# STM32F030C8T6.net
KiCad netlist of a schematic drawn in Altium Designer
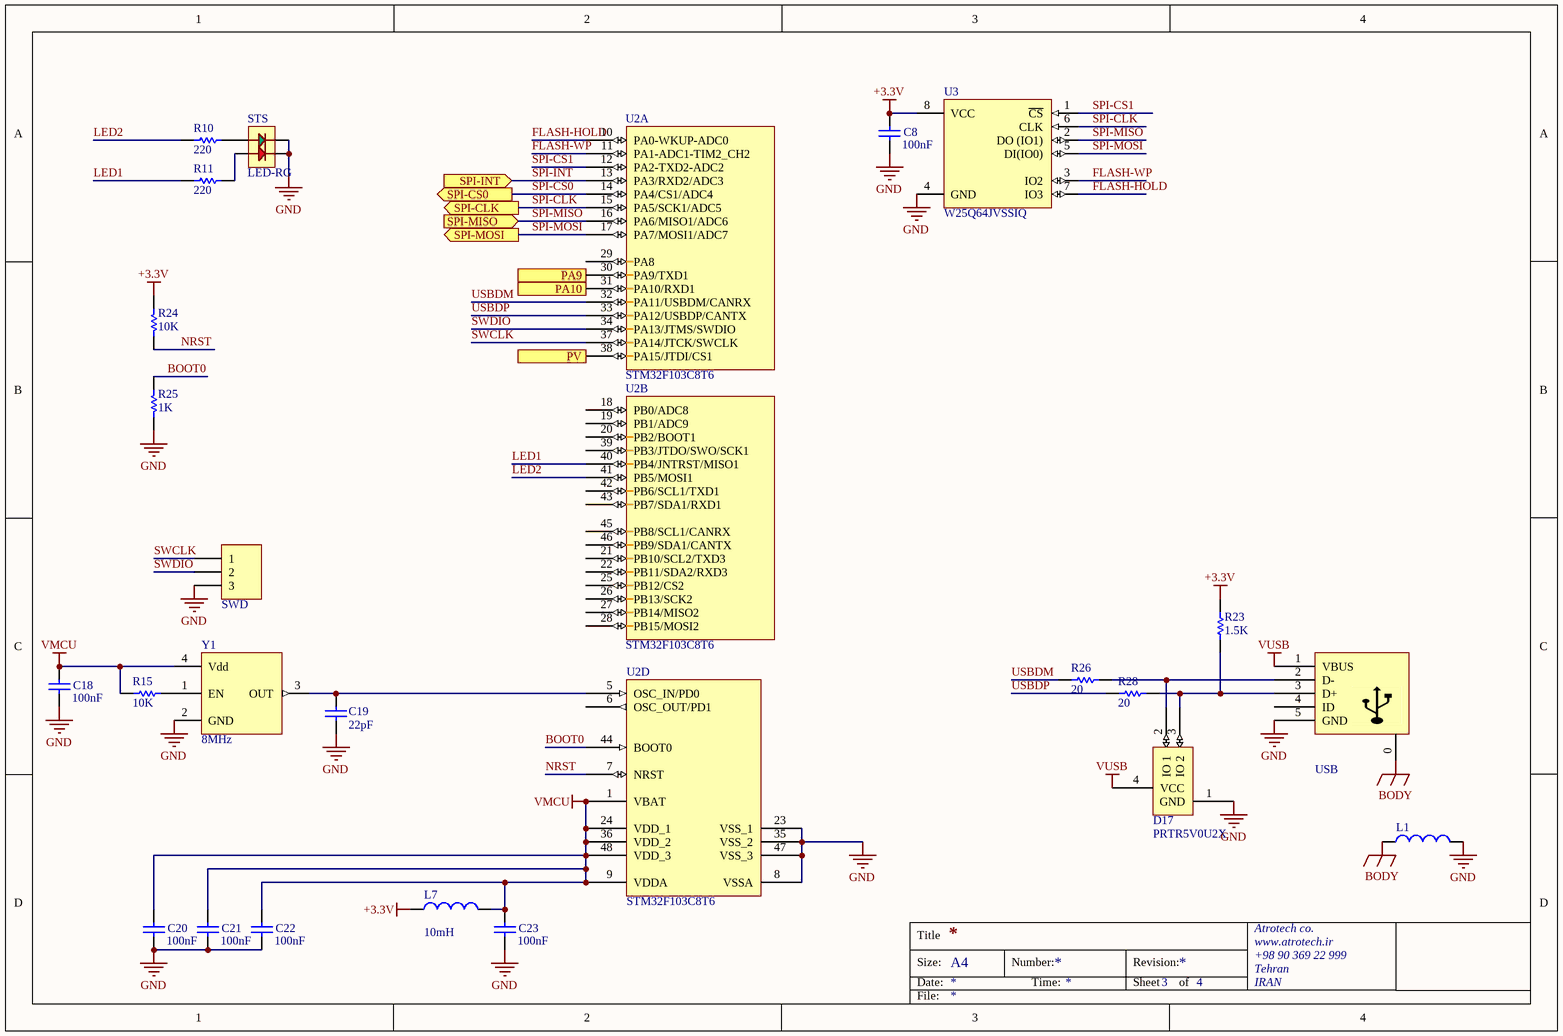
[diagram p0: STM32F030C8T6.SchDoc]

(export (version "E")
  (design (tool "Eeschema 10.0.6"))
  (components
    (comp (ref "C8")
      (value "100nF")
      (footprint "C603")
      (description "Capacitor")
      (fields (field (name "DESIGNER") "Parsa Malekpour"))
      (libsource (lib "UserPKG") (part "Cap"))
    )
    (comp (ref "C18")
      (value "100nF")
      (footprint "C603")
      (description "Capacitor")
      (fields (field (name "DESIGNER") "Parsa Malekpour"))
      (libsource (lib "UserPKG") (part "Cap"))
    )
    (comp (ref "C19")
      (value "22pF")
      (footprint "C603")
      (description "Capacitor")
      (fields (field (name "DESIGNER") "Parsa Malekpour"))
      (libsource (lib "UserPKG") (part "Cap"))
    )
    (comp (ref "C20")
      (value "100nF")
      (footprint "C603")
      (description "Capacitor")
      (fields (field (name "DESIGNER") "Parsa Malekpour"))
      (libsource (lib "UserPKG") (part "Cap"))
    )
    (comp (ref "C21")
      (value "100nF")
      (footprint "C603")
      (description "Capacitor")
      (fields (field (name "DESIGNER") "Parsa Malekpour"))
      (libsource (lib "UserPKG") (part "Cap"))
    )
    (comp (ref "C22")
      (value "100nF")
      (footprint "C603")
      (description "Capacitor")
      (fields (field (name "DESIGNER") "Parsa Malekpour"))
      (libsource (lib "UserPKG") (part "Cap"))
    )
    (comp (ref "C23")
      (value "100nF")
      (footprint "C603")
      (description "Capacitor")
      (fields (field (name "DESIGNER") "Parsa Malekpour"))
      (libsource (lib "UserPKG") (part "Cap"))
    )
    (comp (ref "D17")
      (value "PRTR5V0U2X")
      (footprint "SOT-143B")
      (description "Ultra low capacitance double rail-to-rail ESD protection diode")
      (libsource (lib "ParsaLibrary") (part "PRTR5V0U2X"))
    )
    (comp (ref "L1")
      (value "Inductor")
      (footprint "R805")
      (fields (field (name "PUBLISHER") "Altium Limited"))
      (libsource (lib "Miscellaneous Devices") (part "Inductor"))
    )
    (comp (ref "L7")
      (value "10mH")
      (footprint "R805")
      (description "Inductor")
      (fields (field (name "PUBLISHER") "Altium Limited"))
      (libsource (lib "Miscellaneous Devices") (part "Inductor"))
    )
    (comp (ref "R10")
      (value "220")
      (footprint "R0603")
      (description "Resistor")
      (fields (field (name "DESIGNER") "Parsa Malekpour"))
      (libsource (lib "ParsaLibrary") (part "Resistor"))
    )
    (comp (ref "R11")
      (value "220")
      (footprint "R0603")
      (description "Resistor")
      (fields (field (name "DESIGNER") "Parsa Malekpour"))
      (libsource (lib "ParsaLibrary") (part "Resistor"))
    )
    (comp (ref "R15")
      (value "10K")
      (footprint "R0603")
      (description "Resistor")
      (fields (field (name "DESIGNER") "Parsa Malekpour"))
      (libsource (lib "ParsaLibrary") (part "Resistor"))
    )
    (comp (ref "R23")
      (value "1.5K")
      (footprint "R0603")
      (description "Resistor")
      (fields (field (name "DESIGNER") "Parsa Malekpour"))
      (libsource (lib "ParsaLibrary") (part "Resistor"))
    )
    (comp (ref "R24")
      (value "10K")
      (footprint "R0603")
      (description "Resistor")
      (fields (field (name "DESIGNER") "Parsa Malekpour"))
      (libsource (lib "UserPKG") (part "Resistor"))
    )
    (comp (ref "R25")
      (value "1K")
      (footprint "R0603")
      (description "Resistor")
      (fields (field (name "DESIGNER") "Parsa Malekpour"))
      (libsource (lib "UserPKG") (part "Resistor"))
    )
    (comp (ref "R26")
      (value "20")
      (footprint "R0603")
      (description "Resistor")
      (fields (field (name "DESIGNER") "Parsa Malekpour"))
      (libsource (lib "ParsaLibrary") (part "Resistor"))
    )
    (comp (ref "R28")
      (value "20")
      (footprint "R0603")
      (description "Resistor")
      (fields (field (name "DESIGNER") "Parsa Malekpour"))
      (libsource (lib "ParsaLibrary") (part "Resistor"))
    )
    (comp (ref "STS")
      (value "LED-RG")
      (footprint "LED-1210")
      (libsource (lib "ParsaLibrary") (part "LED-RG-4"))
    )
    (comp (ref "SWD")
      (value "CONN-3")
      (footprint "PHDR3")
      (description "Header, 3-Pin")
      (libsource (lib "ParsaLibrary") (part "CONN-3"))
    )
    (comp (ref "U2")
      (value "STM32F103C8T6")
      (footprint "LQFP-48")
      (description "STM32 ARM-based 32-bit MCU with 64 Kbytes Flash, 48-pin LQFP, Industrial Temperature")
      (fields (field (name "PUBLISHER") "Altium Limited"))
      (libsource (lib "ParsaLibrary") (part "STM32F103C8T6"))
    )
    (comp (ref "U3")
      (value "W25Q64JVSSIQ")
      (footprint "SOIC-8W")
      (libsource (lib "ParsaLibrary") (part "W25Q64JVSSIQ"))
    )
    (comp (ref "USB")
      (value "USB MINI")
      (footprint "USB-MINI-SMD")
      (libsource (lib "ParsaLibrary") (part "USB MINI"))
    )
    (comp (ref "Y1")
      (value "8MHz")
      (footprint "ASV")
      (description "OSCILLATOR")
      (fields (field (name "FREQUENCY") "8MHz"))
      (libsource (lib "ParsaLibrary") (part "OSCILLATOR"))
    )
  )
  (nets
    (net (code "1") (name "+3.3V") (class "Default")
      (node (ref "C8") (pin "2") (pinfunction "2_2") (pintype "passive"))
      (node (ref "L7") (pin "1") (pinfunction "1_1") (pintype "passive"))
      (node (ref "R23") (pin "1") (pinfunction "1_1") (pintype "passive"))
      (node (ref "R24") (pin "2") (pinfunction "2_2") (pintype "passive"))
      (node (ref "U3") (pin "8") (pinfunction "VCC_8") (pintype "power_in"))
    )
    (net (code "2") (name "/BOOT0") (class "Default")
      (node (ref "R25") (pin "2") (pinfunction "2_2") (pintype "passive"))
      (node (ref "U2") (pin "44") (pinfunction "BOOT0_44") (pintype "input"))
    )
    (net (code "3") (name "/FLASH-HOLD") (class "Default")
      (node (ref "U2") (pin "10") (pinfunction "PA0-WKUP-ADC0_10") (pintype "bidirectional"))
      (node (ref "U3") (pin "7") (pinfunction "IO3_7") (pintype "bidirectional"))
    )
    (net (code "4") (name "/FLASH-WP") (class "Default")
      (node (ref "U2") (pin "11") (pinfunction "PA1-ADC1-TIM2_CH2_11") (pintype "bidirectional"))
      (node (ref "U3") (pin "3") (pinfunction "IO2_3") (pintype "bidirectional"))
    )
    (net (code "5") (name "/LED1") (class "Default")
      (node (ref "R11") (pin "2") (pinfunction "2_2") (pintype "passive"))
      (node (ref "U2") (pin "40") (pinfunction "PB4/JNTRST/MISO1_40") (pintype "bidirectional"))
    )
    (net (code "6") (name "/LED2") (class "Default")
      (node (ref "R10") (pin "2") (pinfunction "2_2") (pintype "passive"))
      (node (ref "U2") (pin "41") (pinfunction "PB5/MOSI1_41") (pintype "bidirectional"))
    )
    (net (code "7") (name "/NRST") (class "Default")
      (node (ref "R24") (pin "1") (pinfunction "1_1") (pintype "passive"))
      (node (ref "U2") (pin "7") (pinfunction "NRST_7") (pintype "bidirectional"))
    )
    (net (code "8") (name "/PA9") (class "Default")
      (node (ref "U2") (pin "30") (pinfunction "PA9/TXD1_30") (pintype "bidirectional"))
    )
    (net (code "9") (name "/PA10") (class "Default")
      (node (ref "U2") (pin "31") (pinfunction "PA10/RXD1_31") (pintype "bidirectional"))
    )
    (net (code "10") (name "/PV") (class "Default")
      (node (ref "U2") (pin "38") (pinfunction "PA15/JTDI/CS1_38") (pintype "bidirectional"))
    )
    (net (code "11") (name "/SPI-CLK") (class "Default")
      (node (ref "U2") (pin "15") (pinfunction "PA5/SCK1/ADC5_15") (pintype "bidirectional"))
      (node (ref "U3") (pin "6") (pinfunction "CLK_6") (pintype "input"))
    )
    (net (code "12") (name "/SPI-CS0") (class "Default")
      (node (ref "U2") (pin "14") (pinfunction "PA4/CS1/ADC4_14") (pintype "bidirectional"))
    )
    (net (code "13") (name "/SPI-CS1") (class "Default")
      (node (ref "U2") (pin "12") (pinfunction "PA2-TXD2-ADC2_12") (pintype "bidirectional"))
      (node (ref "U3") (pin "1") (pinfunction "~{CS}_1") (pintype "input"))
    )
    (net (code "14") (name "/SPI-INT") (class "Default")
      (node (ref "U2") (pin "13") (pinfunction "PA3/RXD2/ADC3_13") (pintype "bidirectional"))
    )
    (net (code "15") (name "/SPI-MISO") (class "Default")
      (node (ref "U2") (pin "16") (pinfunction "PA6/MISO1/ADC6_16") (pintype "bidirectional"))
      (node (ref "U3") (pin "2") (pinfunction "DO_(IO1)_2") (pintype "bidirectional"))
    )
    (net (code "16") (name "/SPI-MOSI") (class "Default")
      (node (ref "U2") (pin "17") (pinfunction "PA7/MOSI1/ADC7_17") (pintype "bidirectional"))
      (node (ref "U3") (pin "5") (pinfunction "DI(IO0)_5") (pintype "bidirectional"))
    )
    (net (code "17") (name "/SWCLK") (class "Default")
      (node (ref "SWD") (pin "1") (pinfunction "1_1") (pintype "passive"))
      (node (ref "U2") (pin "37") (pinfunction "PA14/JTCK/SWCLK_37") (pintype "bidirectional"))
    )
    (net (code "18") (name "/SWDIO") (class "Default")
      (node (ref "SWD") (pin "2") (pinfunction "2_2") (pintype "passive"))
      (node (ref "U2") (pin "34") (pinfunction "PA13/JTMS/SWDIO_34") (pintype "bidirectional"))
    )
    (net (code "19") (name "/USBDM") (class "Default")
      (node (ref "R26") (pin "2") (pinfunction "2_2") (pintype "passive"))
      (node (ref "U2") (pin "32") (pinfunction "PA11/USBDM/CANRX_32") (pintype "bidirectional"))
    )
    (net (code "20") (name "/USBDP") (class "Default")
      (node (ref "R28") (pin "2") (pinfunction "2_2") (pintype "passive"))
      (node (ref "U2") (pin "33") (pinfunction "PA12/USBDP/CANTX_33") (pintype "bidirectional"))
    )
    (net (code "21") (name "BODY") (class "Default")
      (node (ref "L1") (pin "1") (pinfunction "1_1") (pintype "passive"))
      (node (ref "USB") (pin "0") (pinfunction "BODY_0") (pintype "passive"))
    )
    (net (code "22") (name "GND") (class "Default")
      (node (ref "C18") (pin "1") (pinfunction "1_1") (pintype "passive"))
      (node (ref "C19") (pin "2") (pinfunction "2_2") (pintype "passive"))
      (node (ref "C20") (pin "1") (pinfunction "1_1") (pintype "passive"))
      (node (ref "C21") (pin "1") (pinfunction "1_1") (pintype "passive"))
      (node (ref "C22") (pin "1") (pinfunction "1_1") (pintype "passive"))
      (node (ref "C23") (pin "1") (pinfunction "1_1") (pintype "passive"))
      (node (ref "C8") (pin "1") (pinfunction "1_1") (pintype "passive"))
      (node (ref "D17") (pin "1") (pinfunction "GND_1") (pintype "power_in"))
      (node (ref "L1") (pin "2") (pinfunction "2_2") (pintype "passive"))
      (node (ref "R25") (pin "1") (pinfunction "1_1") (pintype "passive"))
      (node (ref "STS") (pin "3") (pinfunction "RED-C_3") (pintype "passive"))
      (node (ref "STS") (pin "4") (pinfunction "GRN-C_4") (pintype "passive"))
      (node (ref "SWD") (pin "3") (pinfunction "3_3") (pintype "passive"))
      (node (ref "U2") (pin "23") (pinfunction "VSS_1_23") (pintype "power_in"))
      (node (ref "U2") (pin "35") (pinfunction "VSS_2_35") (pintype "power_in"))
      (node (ref "U2") (pin "47") (pinfunction "VSS_3_47") (pintype "power_in"))
      (node (ref "U2") (pin "8") (pinfunction "VSSA_8") (pintype "power_in"))
      (node (ref "U3") (pin "4") (pinfunction "GND_4") (pintype "power_in"))
      (node (ref "USB") (pin "5") (pinfunction "GND_5") (pintype "power_in"))
      (node (ref "Y1") (pin "2") (pinfunction "GND_2") (pintype "passive"))
    )
    (net (code "23") (name "Net-(D17-IO_1)") (class "Default")
      (node (ref "D17") (pin "2") (pinfunction "IO_1_2") (pintype "bidirectional"))
      (node (ref "R26") (pin "1") (pinfunction "1_1") (pintype "passive"))
      (node (ref "USB") (pin "2") (pinfunction "D-_2") (pintype "passive"))
    )
    (net (code "24") (name "Net-(D17-IO_2)") (class "Default")
      (node (ref "D17") (pin "3") (pinfunction "IO_2_3") (pintype "bidirectional"))
      (node (ref "R23") (pin "2") (pinfunction "2_2") (pintype "passive"))
      (node (ref "R28") (pin "1") (pinfunction "1_1") (pintype "passive"))
      (node (ref "USB") (pin "3") (pinfunction "D+_3") (pintype "passive"))
    )
    (net (code "25") (name "Net-(STS-GRN-A)") (class "Default")
      (node (ref "R10") (pin "1") (pinfunction "1_1") (pintype "passive"))
      (node (ref "STS") (pin "1") (pinfunction "GRN-A_1") (pintype "passive"))
    )
    (net (code "26") (name "Net-(STS-RED-A)") (class "Default")
      (node (ref "R11") (pin "1") (pinfunction "1_1") (pintype "passive"))
      (node (ref "STS") (pin "2") (pinfunction "RED-A_2") (pintype "passive"))
    )
    (net (code "27") (name "Net-(U2D-OSC_IN{slash}PD0)") (class "Default")
      (node (ref "C19") (pin "1") (pinfunction "1_1") (pintype "passive"))
      (node (ref "U2") (pin "5") (pinfunction "OSC_IN/PD0_5") (pintype "input"))
      (node (ref "Y1") (pin "3") (pinfunction "OUT_3") (pintype "output"))
    )
    (net (code "28") (name "Net-(Y1-EN)") (class "Default")
      (node (ref "R15") (pin "1") (pinfunction "1_1") (pintype "passive"))
      (node (ref "Y1") (pin "1") (pinfunction "EN_1") (pintype "passive"))
    )
    (net (code "29") (name "VMCU") (class "Default")
      (node (ref "C18") (pin "2") (pinfunction "2_2") (pintype "passive"))
      (node (ref "C20") (pin "2") (pinfunction "2_2") (pintype "passive"))
      (node (ref "C21") (pin "2") (pinfunction "2_2") (pintype "passive"))
      (node (ref "C22") (pin "2") (pinfunction "2_2") (pintype "passive"))
      (node (ref "C23") (pin "2") (pinfunction "2_2") (pintype "passive"))
      (node (ref "L7") (pin "2") (pinfunction "2_2") (pintype "passive"))
      (node (ref "R15") (pin "2") (pinfunction "2_2") (pintype "passive"))
      (node (ref "U2") (pin "1") (pinfunction "VBAT_1") (pintype "power_in"))
      (node (ref "U2") (pin "24") (pinfunction "VDD_1_24") (pintype "power_in"))
      (node (ref "U2") (pin "36") (pinfunction "VDD_2_36") (pintype "power_in"))
      (node (ref "U2") (pin "48") (pinfunction "VDD_3_48") (pintype "power_in"))
      (node (ref "U2") (pin "9") (pinfunction "VDDA_9") (pintype "power_in"))
      (node (ref "Y1") (pin "4") (pinfunction "Vdd_4") (pintype "passive"))
    )
    (net (code "30") (name "VUSB") (class "Default")
      (node (ref "D17") (pin "4") (pinfunction "VCC_4") (pintype "power_in"))
      (node (ref "USB") (pin "1") (pinfunction "VBUS_1") (pintype "power_in"))
    )
    (net (code "31") (name "unconnected-(U2A-PA8-Pad29)") (class "Default")
      (node (ref "U2") (pin "29") (pinfunction "PA8_29") (pintype "bidirectional"))
    )
    (net (code "32") (name "unconnected-(U2B-PB0{slash}ADC8-Pad18)") (class "Default")
      (node (ref "U2") (pin "18") (pinfunction "PB0/ADC8_18") (pintype "bidirectional"))
    )
    (net (code "33") (name "unconnected-(U2B-PB1{slash}ADC9-Pad19)") (class "Default")
      (node (ref "U2") (pin "19") (pinfunction "PB1/ADC9_19") (pintype "bidirectional"))
    )
    (net (code "34") (name "unconnected-(U2B-PB2{slash}BOOT1-Pad20)") (class "Default")
      (node (ref "U2") (pin "20") (pinfunction "PB2/BOOT1_20") (pintype "bidirectional"))
    )
    (net (code "35") (name "unconnected-(U2B-PB3{slash}JTDO{slash}SWO{slash}SCK1-Pad39)") (class "Default")
      (node (ref "U2") (pin "39") (pinfunction "PB3/JTDO/SWO/SCK1_39") (pintype "bidirectional"))
    )
    (net (code "36") (name "unconnected-(U2B-PB6{slash}SCL1{slash}TXD1-Pad42)") (class "Default")
      (node (ref "U2") (pin "42") (pinfunction "PB6/SCL1/TXD1_42") (pintype "bidirectional"))
    )
    (net (code "37") (name "unconnected-(U2B-PB7{slash}SDA1{slash}RXD1-Pad43)") (class "Default")
      (node (ref "U2") (pin "43") (pinfunction "PB7/SDA1/RXD1_43") (pintype "bidirectional"))
    )
    (net (code "38") (name "unconnected-(U2B-PB8{slash}SCL1{slash}CANRX-Pad45)") (class "Default")
      (node (ref "U2") (pin "45") (pinfunction "PB8/SCL1/CANRX_45") (pintype "bidirectional"))
    )
    (net (code "39") (name "unconnected-(U2B-PB9{slash}SDA1{slash}CANTX-Pad46)") (class "Default")
      (node (ref "U2") (pin "46") (pinfunction "PB9/SDA1/CANTX_46") (pintype "bidirectional"))
    )
    (net (code "40") (name "unconnected-(U2B-PB10{slash}SCL2{slash}TXD3-Pad21)") (class "Default")
      (node (ref "U2") (pin "21") (pinfunction "PB10/SCL2/TXD3_21") (pintype "bidirectional"))
    )
    (net (code "41") (name "unconnected-(U2B-PB11{slash}SDA2{slash}RXD3-Pad22)") (class "Default")
      (node (ref "U2") (pin "22") (pinfunction "PB11/SDA2/RXD3_22") (pintype "bidirectional"))
    )
    (net (code "42") (name "unconnected-(U2B-PB12{slash}CS2-Pad25)") (class "Default")
      (node (ref "U2") (pin "25") (pinfunction "PB12/CS2_25") (pintype "bidirectional"))
    )
    (net (code "43") (name "unconnected-(U2B-PB13{slash}SCK2-Pad26)") (class "Default")
      (node (ref "U2") (pin "26") (pinfunction "PB13/SCK2_26") (pintype "bidirectional"))
    )
    (net (code "44") (name "unconnected-(U2B-PB14{slash}MISO2-Pad27)") (class "Default")
      (node (ref "U2") (pin "27") (pinfunction "PB14/MISO2_27") (pintype "bidirectional"))
    )
    (net (code "45") (name "unconnected-(U2B-PB15{slash}MOSI2-Pad28)") (class "Default")
      (node (ref "U2") (pin "28") (pinfunction "PB15/MOSI2_28") (pintype "bidirectional"))
    )
    (net (code "46") (name "unconnected-(U2D-OSC_OUT{slash}PD1-Pad6)") (class "Default")
      (node (ref "U2") (pin "6") (pinfunction "OSC_OUT/PD1_6") (pintype "output"))
    )
    (net (code "47") (name "unconnected-(USB-ID-Pad4)") (class "Default")
      (node (ref "USB") (pin "4") (pinfunction "ID_4") (pintype "power_in"))
    )
  )
)
